# V2_lite.net
KiCad netlist of a schematic drawn in EAGLE
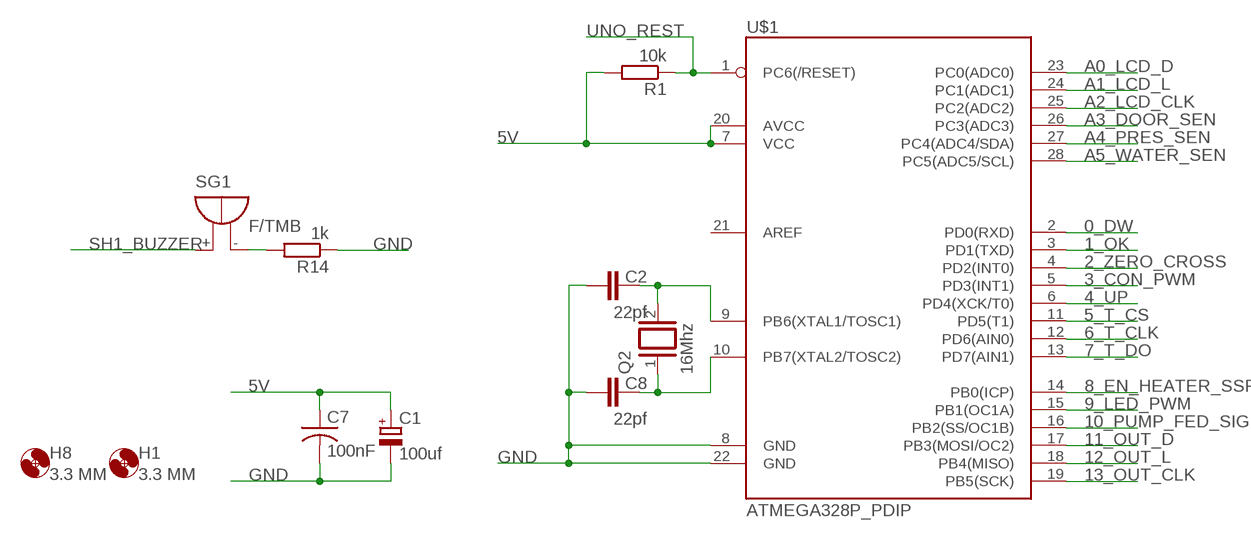
[diagram p0: schematic, sheet 1]
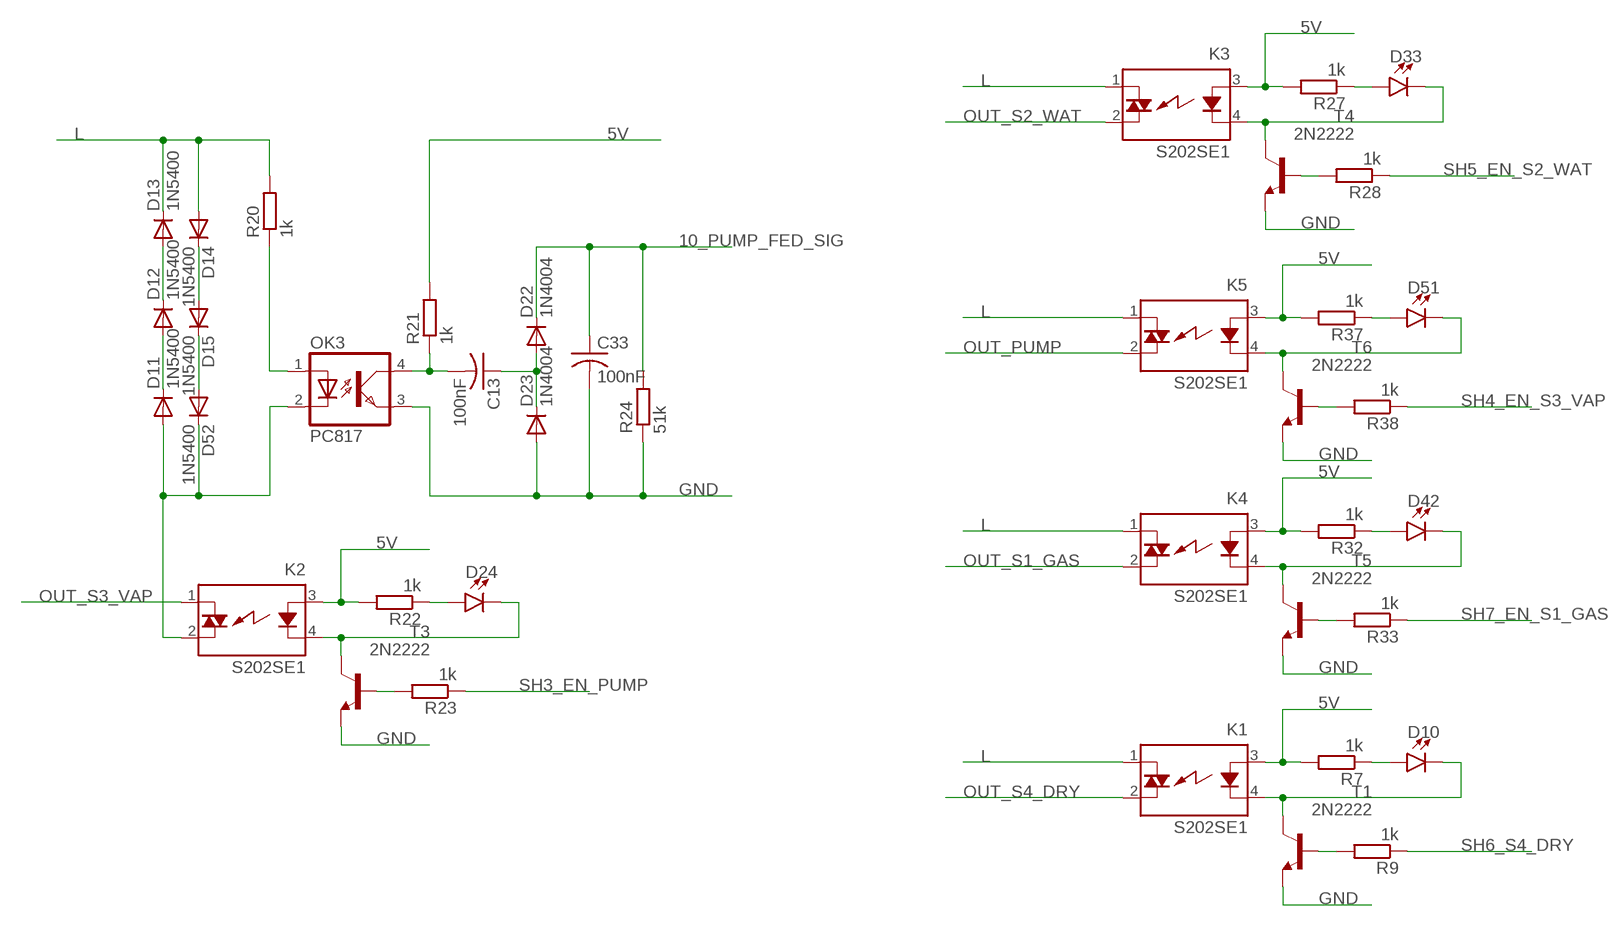
[diagram p1: schematic, sheet 2]
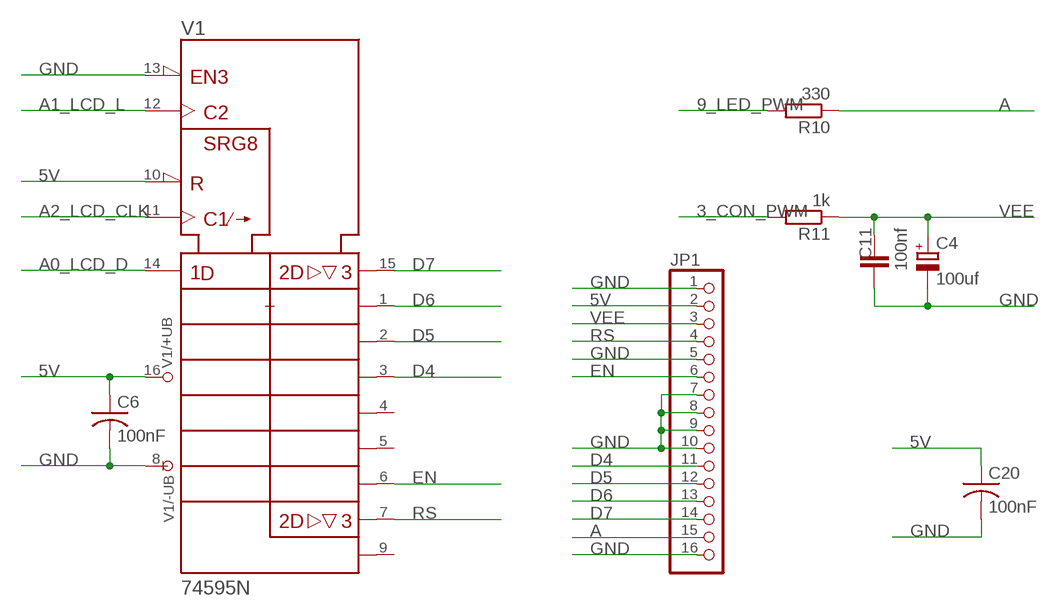
[diagram p2: schematic, sheet 3]
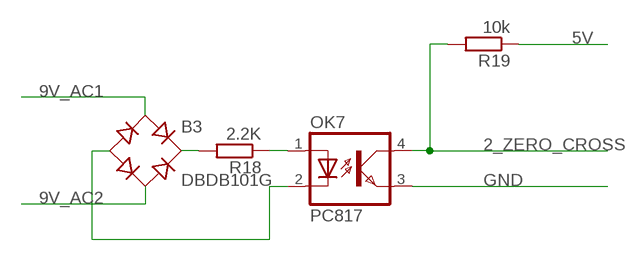
[diagram p3: schematic, sheet 4]
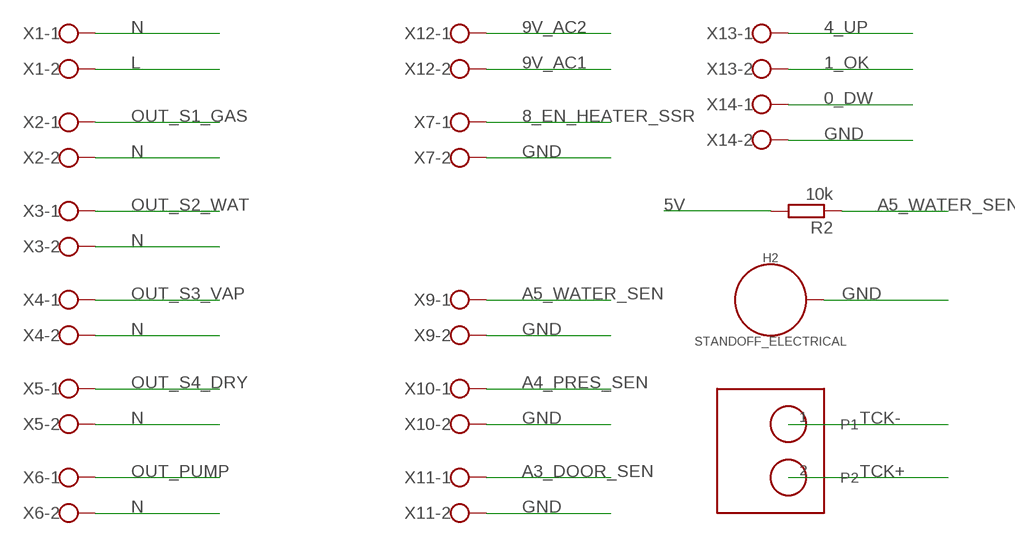
[diagram p4: schematic, sheet 5]
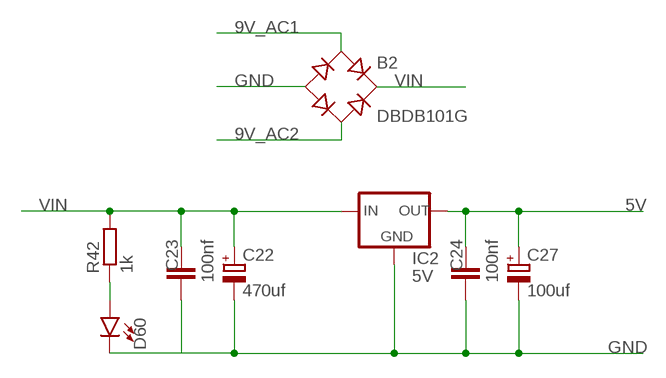
[diagram p5: schematic, sheet 6]
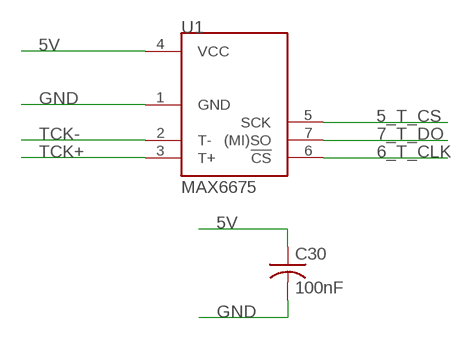
[diagram p6: schematic, sheet 7]
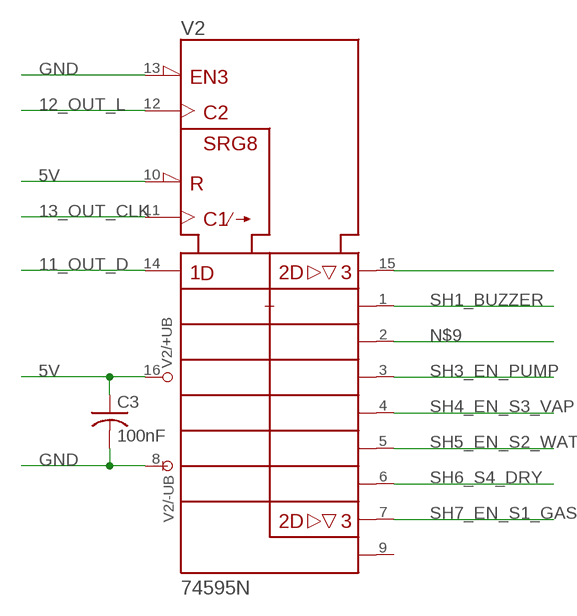
[diagram p7: schematic, sheet 8]

(export (version "E")
  (design (tool "Eeschema 10.0.6"))
  (components
    (comp (ref "C13")
      (value "100nF")
      (footprint "eagle-import:C050-035X075")
      (libsource (lib "eagle-import") (part "C-US050-035X075"))
    )
    (comp (ref "C33")
      (value "100nF")
      (footprint "eagle-import:C050-035X075")
      (libsource (lib "eagle-import") (part "C-US050-035X075"))
    )
    (comp (ref "D10")
      (value "LED5MM")
      (footprint "eagle-import:LED_5MM")
      (libsource (lib "eagle-import") (part "LED5MM"))
    )
    (comp (ref "D11")
      (value "1N5400")
      (footprint "eagle-import:DO201-15")
      (libsource (lib "eagle-import") (part "1N5400"))
    )
    (comp (ref "D12")
      (value "1N5400")
      (footprint "eagle-import:DO201-15")
      (libsource (lib "eagle-import") (part "1N5400"))
    )
    (comp (ref "D13")
      (value "1N5400")
      (footprint "eagle-import:DO201-15")
      (libsource (lib "eagle-import") (part "1N5400"))
    )
    (comp (ref "D14")
      (value "1N5400")
      (footprint "eagle-import:DO201-15")
      (libsource (lib "eagle-import") (part "1N5400"))
    )
    (comp (ref "D15")
      (value "1N5400")
      (footprint "eagle-import:DO201-15")
      (libsource (lib "eagle-import") (part "1N5400"))
    )
    (comp (ref "D22")
      (value "1N4004")
      (footprint "eagle-import:DO41-10")
      (libsource (lib "eagle-import") (part "1N4004"))
    )
    (comp (ref "D23")
      (value "1N4004")
      (footprint "eagle-import:DO41-10")
      (libsource (lib "eagle-import") (part "1N4004"))
    )
    (comp (ref "D24")
      (value "LED5MM")
      (footprint "eagle-import:LED_5MM")
      (libsource (lib "eagle-import") (part "LED5MM"))
    )
    (comp (ref "D33")
      (value "LED5MM")
      (footprint "eagle-import:LED_5MM")
      (libsource (lib "eagle-import") (part "LED5MM"))
    )
    (comp (ref "D42")
      (value "LED5MM")
      (footprint "eagle-import:LED_5MM")
      (libsource (lib "eagle-import") (part "LED5MM"))
    )
    (comp (ref "D51")
      (value "LED5MM")
      (footprint "eagle-import:LED_5MM")
      (libsource (lib "eagle-import") (part "LED5MM"))
    )
    (comp (ref "D52")
      (value "1N5400")
      (footprint "eagle-import:DO201-15")
      (libsource (lib "eagle-import") (part "1N5400"))
    )
    (comp (ref "K1")
      (value "S202SE1")
      (footprint "eagle-import:S2XXEX")
      (libsource (lib "eagle-import") (part "S202SE1"))
    )
    (comp (ref "K2")
      (value "S202SE1")
      (footprint "eagle-import:S2XXEX")
      (libsource (lib "eagle-import") (part "S202SE1"))
    )
    (comp (ref "K3")
      (value "S202SE1")
      (footprint "eagle-import:S2XXEX")
      (libsource (lib "eagle-import") (part "S202SE1"))
    )
    (comp (ref "K4")
      (value "S202SE1")
      (footprint "eagle-import:S2XXEX")
      (libsource (lib "eagle-import") (part "S202SE1"))
    )
    (comp (ref "K5")
      (value "S202SE1")
      (footprint "eagle-import:S2XXEX")
      (libsource (lib "eagle-import") (part "S202SE1"))
    )
    (comp (ref "OK3")
      (value "PC817")
      (footprint "eagle-import:DIL04")
      (libsource (lib "eagle-import") (part "PC817"))
    )
    (comp (ref "R7")
      (value "1k")
      (footprint "eagle-import:0207_10")
      (libsource (lib "eagle-import") (part "R-EU_0207/10"))
    )
    (comp (ref "R9")
      (value "1k")
      (footprint "eagle-import:0207_10")
      (libsource (lib "eagle-import") (part "R-EU_0207/10"))
    )
    (comp (ref "R20")
      (value "1k")
      (footprint "eagle-import:0207_10")
      (libsource (lib "eagle-import") (part "R-EU_0207/10"))
    )
    (comp (ref "R21")
      (value "1k")
      (footprint "eagle-import:0207_10")
      (libsource (lib "eagle-import") (part "R-EU_0207/10"))
    )
    (comp (ref "R22")
      (value "1k")
      (footprint "eagle-import:0207_10")
      (libsource (lib "eagle-import") (part "R-EU_0207/10"))
    )
    (comp (ref "R23")
      (value "1k")
      (footprint "eagle-import:0207_10")
      (libsource (lib "eagle-import") (part "R-EU_0207/10"))
    )
    (comp (ref "R24")
      (value "51k")
      (footprint "eagle-import:0207_10")
      (libsource (lib "eagle-import") (part "R-EU_0207/10"))
    )
    (comp (ref "R27")
      (value "1k")
      (footprint "eagle-import:0207_10")
      (libsource (lib "eagle-import") (part "R-EU_0207/10"))
    )
    (comp (ref "R28")
      (value "1k")
      (footprint "eagle-import:0207_10")
      (libsource (lib "eagle-import") (part "R-EU_0207/10"))
    )
    (comp (ref "R32")
      (value "1k")
      (footprint "eagle-import:0207_10")
      (libsource (lib "eagle-import") (part "R-EU_0207/10"))
    )
    (comp (ref "R33")
      (value "1k")
      (footprint "eagle-import:0207_10")
      (libsource (lib "eagle-import") (part "R-EU_0207/10"))
    )
    (comp (ref "R37")
      (value "1k")
      (footprint "eagle-import:0207_10")
      (libsource (lib "eagle-import") (part "R-EU_0207/10"))
    )
    (comp (ref "R38")
      (value "1k")
      (footprint "eagle-import:0207_10")
      (libsource (lib "eagle-import") (part "R-EU_0207/10"))
    )
    (comp (ref "T1")
      (value "2N2222")
      (footprint "eagle-import:TO92-EBC-OVAL")
      (libsource (lib "eagle-import") (part "2N2222"))
    )
    (comp (ref "T3")
      (value "2N2222")
      (footprint "eagle-import:TO92-EBC-OVAL")
      (libsource (lib "eagle-import") (part "2N2222"))
    )
    (comp (ref "T4")
      (value "2N2222")
      (footprint "eagle-import:TO92-EBC-OVAL")
      (libsource (lib "eagle-import") (part "2N2222"))
    )
    (comp (ref "T5")
      (value "2N2222")
      (footprint "eagle-import:TO92-EBC-OVAL")
      (libsource (lib "eagle-import") (part "2N2222"))
    )
    (comp (ref "T6")
      (value "2N2222")
      (footprint "eagle-import:TO92-EBC-OVAL")
      (libsource (lib "eagle-import") (part "2N2222"))
    )
    (comp (ref "C30")
      (value "100nF")
      (footprint "eagle-import:C050-035X075")
      (libsource (lib "eagle-import") (part "C-US050-035X075"))
    )
    (comp (ref "U1")
      (value "MAX6675")
      (footprint "eagle-import:SOIC8")
      (libsource (lib "eagle-import") (part "MAX6675"))
    )
    (comp (ref "H2")
      (value "STANDOFF_ELECTRICAL")
      (footprint "eagle-import:STANDOFF-ELECTRICAL")
      (libsource (lib "eagle-import") (part "STANDOFF_ELECTRICAL"))
    )
    (comp (ref "R2")
      (value "10k")
      (footprint "eagle-import:0207_10")
      (libsource (lib "eagle-import") (part "R-EU_0207/10"))
    )
    (comp (ref "U$2")
      (value "THERMO_CONNECT")
      (footprint "eagle-import:HW-550")
      (libsource (lib "eagle-import") (part "THERMO_CONNECT"))
    )
    (comp (ref "X1")
      (value "W237-102")
      (footprint "eagle-import:W237-102")
      (fields (field (name "MPN") "237-102"))
      (libsource (lib "eagle-import") (part "W237-102"))
    )
    (comp (ref "X2")
      (value "W237-102")
      (footprint "eagle-import:W237-102")
      (fields (field (name "MPN") "237-102"))
      (libsource (lib "eagle-import") (part "W237-102"))
    )
    (comp (ref "X3")
      (value "W237-102")
      (footprint "eagle-import:W237-102")
      (fields (field (name "MPN") "237-102"))
      (libsource (lib "eagle-import") (part "W237-102"))
    )
    (comp (ref "X4")
      (value "W237-102")
      (footprint "eagle-import:W237-102")
      (fields (field (name "MPN") "237-102"))
      (libsource (lib "eagle-import") (part "W237-102"))
    )
    (comp (ref "X5")
      (value "W237-102")
      (footprint "eagle-import:W237-102")
      (fields (field (name "MPN") "237-102"))
      (libsource (lib "eagle-import") (part "W237-102"))
    )
    (comp (ref "X6")
      (value "W237-102")
      (footprint "eagle-import:W237-102")
      (fields (field (name "MPN") "237-102"))
      (libsource (lib "eagle-import") (part "W237-102"))
    )
    (comp (ref "X7")
      (value "W237-102")
      (footprint "eagle-import:W237-102")
      (fields (field (name "MPN") "237-102"))
      (libsource (lib "eagle-import") (part "W237-102"))
    )
    (comp (ref "X9")
      (value "W237-102")
      (footprint "eagle-import:W237-102")
      (fields (field (name "MPN") "237-102"))
      (libsource (lib "eagle-import") (part "W237-102"))
    )
    (comp (ref "X10")
      (value "W237-102")
      (footprint "eagle-import:W237-102")
      (fields (field (name "MPN") "237-102"))
      (libsource (lib "eagle-import") (part "W237-102"))
    )
    (comp (ref "X11")
      (value "W237-102")
      (footprint "eagle-import:W237-102")
      (fields (field (name "MPN") "237-102"))
      (libsource (lib "eagle-import") (part "W237-102"))
    )
    (comp (ref "X12")
      (value "W237-102")
      (footprint "eagle-import:W237-102")
      (fields (field (name "MPN") "237-102"))
      (libsource (lib "eagle-import") (part "W237-102"))
    )
    (comp (ref "X13")
      (value "W237-102")
      (footprint "eagle-import:W237-102")
      (fields (field (name "MPN") "237-102"))
      (libsource (lib "eagle-import") (part "W237-102"))
    )
    (comp (ref "X14")
      (value "W237-102")
      (footprint "eagle-import:W237-102")
      (fields (field (name "MPN") "237-102"))
      (libsource (lib "eagle-import") (part "W237-102"))
    )
    (comp (ref "B2")
      (value "DBDB101G")
      (footprint "eagle-import:DB")
      (libsource (lib "eagle-import") (part "DB?GDB101"))
    )
    (comp (ref "C22")
      (value "470uf")
      (footprint "eagle-import:E3,5-8")
      (libsource (lib "eagle-import") (part "CPOL-EUE3.5-8"))
    )
    (comp (ref "C23")
      (value "100nf")
      (footprint "eagle-import:C050-030X075")
      (libsource (lib "eagle-import") (part "C-EU050-030X075"))
    )
    (comp (ref "C24")
      (value "100nf")
      (footprint "eagle-import:C050-030X075")
      (libsource (lib "eagle-import") (part "C-EU050-030X075"))
    )
    (comp (ref "C27")
      (value "100uf")
      (footprint "eagle-import:E3,5-8")
      (libsource (lib "eagle-import") (part "CPOL-EUE3.5-8"))
    )
    (comp (ref "D60")
      (value "LED5MM")
      (footprint "eagle-import:LED_5MM")
      (libsource (lib "eagle-import") (part "LED5MM"))
    )
    (comp (ref "IC2")
      (value "5V")
      (footprint "eagle-import:78XXL")
      (libsource (lib "eagle-import") (part "V_REG_78XXSIDE"))
    )
    (comp (ref "R42")
      (value "1k")
      (footprint "eagle-import:0207_10")
      (libsource (lib "eagle-import") (part "R-EU_0207/10"))
    )
    (comp (ref "C1")
      (value "100uf")
      (footprint "eagle-import:E3,5-8")
      (libsource (lib "eagle-import") (part "CPOL-EUE3.5-8"))
    )
    (comp (ref "C2")
      (value "22pf")
      (footprint "eagle-import:C050-030X075")
      (libsource (lib "eagle-import") (part "C-EU050-030X075"))
    )
    (comp (ref "C7")
      (value "100nF")
      (footprint "eagle-import:C050-035X075")
      (libsource (lib "eagle-import") (part "C-US050-035X075"))
    )
    (comp (ref "C8")
      (value "22pf")
      (footprint "eagle-import:C050-030X075")
      (libsource (lib "eagle-import") (part "C-EU050-030X075"))
    )
    (comp (ref "H1")
      (value "3.3 MM")
      (footprint "eagle-import:3,3")
      (libsource (lib "eagle-import") (part "MOUNT-HOLE3.3"))
    )
    (comp (ref "H8")
      (value "3.3 MM")
      (footprint "eagle-import:3,3")
      (libsource (lib "eagle-import") (part "MOUNT-HOLE3.3"))
    )
    (comp (ref "Q2")
      (value "16Mhz")
      (footprint "eagle-import:QS")
      (libsource (lib "eagle-import") (part "XTAL/S"))
    )
    (comp (ref "R1")
      (value "10k")
      (footprint "eagle-import:0207_10")
      (libsource (lib "eagle-import") (part "R-EU_0207/10"))
    )
    (comp (ref "R14")
      (value "1k")
      (footprint "eagle-import:0207_10")
      (libsource (lib "eagle-import") (part "R-EU_0207/10"))
    )
    (comp (ref "SG1")
      (value "F/TMB")
      (footprint "eagle-import:F_TMB")
      (libsource (lib "eagle-import") (part "F/TMB"))
    )
    (comp (ref "U$1")
      (value "ATMEGA328P_PDIP")
      (footprint "eagle-import:DIL-28-3")
      (libsource (lib "eagle-import") (part "ATMEGA328P_PDIP"))
    )
    (comp (ref "B3")
      (value "DBDB101G")
      (footprint "eagle-import:DB")
      (libsource (lib "eagle-import") (part "DB?GDB101"))
    )
    (comp (ref "OK7")
      (value "PC817")
      (footprint "eagle-import:DIL04")
      (libsource (lib "eagle-import") (part "PC817"))
    )
    (comp (ref "R18")
      (value "2.2K")
      (footprint "eagle-import:0207_10")
      (libsource (lib "eagle-import") (part "R-EU_0207/10"))
    )
    (comp (ref "R19")
      (value "10k")
      (footprint "eagle-import:0207_10")
      (libsource (lib "eagle-import") (part "R-EU_0207/10"))
    )
    (comp (ref "C3")
      (value "100nF")
      (footprint "eagle-import:C050-035X075")
      (libsource (lib "eagle-import") (part "C-US050-035X075"))
    )
    (comp (ref "V2")
      (value "74595N")
      (footprint "eagle-import:DIL16")
      (libsource (lib "eagle-import") (part "74595N"))
    )
    (comp (ref "C4")
      (value "100uf")
      (footprint "eagle-import:E3,5-8")
      (libsource (lib "eagle-import") (part "CPOL-EUE3.5-8"))
    )
    (comp (ref "C6")
      (value "100nF")
      (footprint "eagle-import:C050-035X075")
      (libsource (lib "eagle-import") (part "C-US050-035X075"))
    )
    (comp (ref "C11")
      (value "100nf")
      (footprint "eagle-import:C050-030X075")
      (libsource (lib "eagle-import") (part "C-EU050-030X075"))
    )
    (comp (ref "C20")
      (value "100nF")
      (footprint "eagle-import:C050-035X075")
      (libsource (lib "eagle-import") (part "C-US050-035X075"))
    )
    (comp (ref "JP1")
      (value "PINHD-1X16")
      (footprint "eagle-import:1X16")
      (libsource (lib "eagle-import") (part "PINHD-1X16"))
    )
    (comp (ref "R10")
      (value "330")
      (footprint "eagle-import:0207_10")
      (libsource (lib "eagle-import") (part "R-EU_0207/10"))
    )
    (comp (ref "R11")
      (value "1k")
      (footprint "eagle-import:0207_10")
      (libsource (lib "eagle-import") (part "R-EU_0207/10"))
    )
    (comp (ref "V1")
      (value "74595N")
      (footprint "eagle-import:DIL16")
      (libsource (lib "eagle-import") (part "74595N"))
    )
  )
  (nets
    (net (code "1") (name "0_DW") (class "Default")
      (node (ref "U$1") (pin "2") (pinfunction "PD0(RXD)_2") (pintype "bidirectional"))
      (node (ref "X14") (pin "1") (pinfunction "KL_1") (pintype "passive"))
    )
    (net (code "2") (name "1_OK") (class "Default")
      (node (ref "U$1") (pin "3") (pinfunction "PD1(TXD)_3") (pintype "bidirectional"))
      (node (ref "X13") (pin "2") (pinfunction "KL_2") (pintype "passive"))
    )
    (net (code "3") (name "2_ZERO_CROSS") (class "Default")
      (node (ref "OK7") (pin "4") (pinfunction "COL_4") (pintype "passive"))
      (node (ref "R19") (pin "2") (pinfunction "2_2") (pintype "passive"))
      (node (ref "U$1") (pin "4") (pinfunction "PD2(INT0)_4") (pintype "bidirectional"))
    )
    (net (code "4") (name "3_CON_PWM") (class "Default")
      (node (ref "R11") (pin "2") (pinfunction "2_2") (pintype "passive"))
      (node (ref "U$1") (pin "5") (pinfunction "PD3(INT1)_5") (pintype "bidirectional"))
    )
    (net (code "5") (name "4_UP") (class "Default")
      (node (ref "U$1") (pin "6") (pinfunction "PD4(XCK/T0)_6") (pintype "bidirectional"))
      (node (ref "X13") (pin "1") (pinfunction "KL_1") (pintype "passive"))
    )
    (net (code "6") (name "5V") (class "Default")
      (node (ref "C1") (pin "+") (pinfunction "+_+") (pintype "passive"))
      (node (ref "C20") (pin "1") (pinfunction "1_1") (pintype "passive"))
      (node (ref "C24") (pin "2") (pinfunction "2_2") (pintype "passive"))
      (node (ref "C27") (pin "+") (pinfunction "+_+") (pintype "passive"))
      (node (ref "C3") (pin "1") (pinfunction "1_1") (pintype "passive"))
      (node (ref "C30") (pin "1") (pinfunction "1_1") (pintype "passive"))
      (node (ref "C6") (pin "1") (pinfunction "1_1") (pintype "passive"))
      (node (ref "C7") (pin "1") (pinfunction "1_1") (pintype "passive"))
      (node (ref "IC2") (pin "OUT") (pinfunction "OUT_OUT") (pintype "output"))
      (node (ref "JP1") (pin "2") (pinfunction "2_2") (pintype "passive"))
      (node (ref "K1") (pin "3") (pinfunction "A_3") (pintype "passive"))
      (node (ref "K2") (pin "3") (pinfunction "A_3") (pintype "passive"))
      (node (ref "K3") (pin "3") (pinfunction "A_3") (pintype "passive"))
      (node (ref "K4") (pin "3") (pinfunction "A_3") (pintype "passive"))
      (node (ref "K5") (pin "3") (pinfunction "A_3") (pintype "passive"))
      (node (ref "R1") (pin "2") (pinfunction "2_2") (pintype "passive"))
      (node (ref "R19") (pin "1") (pinfunction "1_1") (pintype "passive"))
      (node (ref "R2") (pin "2") (pinfunction "2_2") (pintype "passive"))
      (node (ref "R21") (pin "2") (pinfunction "2_2") (pintype "passive"))
      (node (ref "R22") (pin "2") (pinfunction "2_2") (pintype "passive"))
      (node (ref "R27") (pin "2") (pinfunction "2_2") (pintype "passive"))
      (node (ref "R32") (pin "2") (pinfunction "2_2") (pintype "passive"))
      (node (ref "R37") (pin "2") (pinfunction "2_2") (pintype "passive"))
      (node (ref "R7") (pin "2") (pinfunction "2_2") (pintype "passive"))
      (node (ref "U$1") (pin "20") (pinfunction "AVCC_20") (pintype "bidirectional"))
      (node (ref "U$1") (pin "7") (pinfunction "VCC_7") (pintype "bidirectional"))
      (node (ref "U1") (pin "4") (pinfunction "VCC_4") (pintype "bidirectional"))
      (node (ref "V1") (pin "10") (pinfunction "~{SRCLR}_10") (pintype "input"))
      (node (ref "V1") (pin "16") (pinfunction "+UB_16") (pintype "power_in"))
      (node (ref "V2") (pin "10") (pinfunction "~{SRCLR}_10") (pintype "input"))
      (node (ref "V2") (pin "16") (pinfunction "+UB_16") (pintype "power_in"))
    )
    (net (code "7") (name "5_T_CS") (class "Default")
      (node (ref "U$1") (pin "11") (pinfunction "PD5(T1)_11") (pintype "bidirectional"))
      (node (ref "U1") (pin "5") (pinfunction "SCK_5") (pintype "bidirectional"))
    )
    (net (code "8") (name "6_T_CLK") (class "Default")
      (node (ref "U$1") (pin "12") (pinfunction "PD6(AIN0)_12") (pintype "bidirectional"))
      (node (ref "U1") (pin "6") (pinfunction "~{CS}_6") (pintype "bidirectional"))
    )
    (net (code "9") (name "7_T_DO") (class "Default")
      (node (ref "U$1") (pin "13") (pinfunction "PD7(AIN1)_13") (pintype "bidirectional"))
      (node (ref "U1") (pin "7") (pinfunction "(MI)SO_7") (pintype "bidirectional"))
    )
    (net (code "10") (name "8_EN_HEATER_SSR") (class "Default")
      (node (ref "U$1") (pin "14") (pinfunction "PB0(ICP)_14") (pintype "bidirectional"))
      (node (ref "X7") (pin "1") (pinfunction "KL_1") (pintype "passive"))
    )
    (net (code "11") (name "9V_AC1") (class "Default")
      (node (ref "B2") (pin "AC1") (pinfunction "AC1_AC1") (pintype "passive"))
      (node (ref "B3") (pin "AC1") (pinfunction "AC1_AC1") (pintype "passive"))
      (node (ref "X12") (pin "2") (pinfunction "KL_2") (pintype "passive"))
    )
    (net (code "12") (name "9V_AC2") (class "Default")
      (node (ref "B2") (pin "AC2") (pinfunction "AC2_AC2") (pintype "passive"))
      (node (ref "B3") (pin "AC2") (pinfunction "AC2_AC2") (pintype "passive"))
      (node (ref "X12") (pin "1") (pinfunction "KL_1") (pintype "passive"))
    )
    (net (code "13") (name "9_LED_PWM") (class "Default")
      (node (ref "R10") (pin "2") (pinfunction "2_2") (pintype "passive"))
      (node (ref "U$1") (pin "15") (pinfunction "PB1(OC1A)_15") (pintype "bidirectional"))
    )
    (net (code "14") (name "10_PUMP_FED_SIG") (class "Default")
      (node (ref "C33") (pin "1") (pinfunction "1_1") (pintype "passive"))
      (node (ref "D22") (pin "C") (pinfunction "C_C") (pintype "passive"))
      (node (ref "R24") (pin "2") (pinfunction "2_2") (pintype "passive"))
      (node (ref "U$1") (pin "16") (pinfunction "PB2(SS/OC1B)_16") (pintype "bidirectional"))
    )
    (net (code "15") (name "11_OUT_D") (class "Default")
      (node (ref "U$1") (pin "17") (pinfunction "PB3(MOSI/OC2)_17") (pintype "bidirectional"))
      (node (ref "V2") (pin "14") (pinfunction "SER_14") (pintype "input"))
    )
    (net (code "16") (name "12_OUT_L") (class "Default")
      (node (ref "U$1") (pin "18") (pinfunction "PB4(MISO)_18") (pintype "bidirectional"))
      (node (ref "V2") (pin "12") (pinfunction "RCK_12") (pintype "input"))
    )
    (net (code "17") (name "13_OUT_CLK") (class "Default")
      (node (ref "U$1") (pin "19") (pinfunction "PB5(SCK)_19") (pintype "bidirectional"))
      (node (ref "V2") (pin "11") (pinfunction "SRCK_11") (pintype "input"))
    )
    (net (code "18") (name "A") (class "Default")
      (node (ref "JP1") (pin "15") (pinfunction "15_15") (pintype "passive"))
      (node (ref "R10") (pin "1") (pinfunction "1_1") (pintype "passive"))
    )
    (net (code "19") (name "A0_LCD_D") (class "Default")
      (node (ref "U$1") (pin "23") (pinfunction "PC0(ADC0)_23") (pintype "bidirectional"))
      (node (ref "V1") (pin "14") (pinfunction "SER_14") (pintype "input"))
    )
    (net (code "20") (name "A1_LCD_L") (class "Default")
      (node (ref "U$1") (pin "24") (pinfunction "PC1(ADC1)_24") (pintype "bidirectional"))
      (node (ref "V1") (pin "12") (pinfunction "RCK_12") (pintype "input"))
    )
    (net (code "21") (name "A2_LCD_CLK") (class "Default")
      (node (ref "U$1") (pin "25") (pinfunction "PC2(ADC2)_25") (pintype "bidirectional"))
      (node (ref "V1") (pin "11") (pinfunction "SRCK_11") (pintype "input"))
    )
    (net (code "22") (name "A3_DOOR_SEN") (class "Default")
      (node (ref "U$1") (pin "26") (pinfunction "PC3(ADC3)_26") (pintype "bidirectional"))
      (node (ref "X11") (pin "1") (pinfunction "KL_1") (pintype "passive"))
    )
    (net (code "23") (name "A4_PRES_SEN") (class "Default")
      (node (ref "U$1") (pin "27") (pinfunction "PC4(ADC4/SDA)_27") (pintype "bidirectional"))
      (node (ref "X10") (pin "1") (pinfunction "KL_1") (pintype "passive"))
    )
    (net (code "24") (name "A5_WATER_SEN") (class "Default")
      (node (ref "R2") (pin "1") (pinfunction "1_1") (pintype "passive"))
      (node (ref "U$1") (pin "28") (pinfunction "PC5(ADC5/SCL)_28") (pintype "bidirectional"))
      (node (ref "X9") (pin "1") (pinfunction "KL_1") (pintype "passive"))
    )
    (net (code "25") (name "D4") (class "Default")
      (node (ref "JP1") (pin "11") (pinfunction "11_11") (pintype "passive"))
      (node (ref "V1") (pin "3") (pinfunction "QD_3") (pintype "tri_state"))
    )
    (net (code "26") (name "D5") (class "Default")
      (node (ref "JP1") (pin "12") (pinfunction "12_12") (pintype "passive"))
      (node (ref "V1") (pin "2") (pinfunction "QC_2") (pintype "tri_state"))
    )
    (net (code "27") (name "D6") (class "Default")
      (node (ref "JP1") (pin "13") (pinfunction "13_13") (pintype "passive"))
      (node (ref "V1") (pin "1") (pinfunction "QB_1") (pintype "tri_state"))
    )
    (net (code "28") (name "D7") (class "Default")
      (node (ref "JP1") (pin "14") (pinfunction "14_14") (pintype "passive"))
      (node (ref "V1") (pin "15") (pinfunction "QA_15") (pintype "tri_state"))
    )
    (net (code "29") (name "EN") (class "Default")
      (node (ref "JP1") (pin "6") (pinfunction "6_6") (pintype "passive"))
      (node (ref "V1") (pin "6") (pinfunction "QG_6") (pintype "tri_state"))
    )
    (net (code "30") (name "GND") (class "Default")
      (node (ref "B2") (pin "-") (pinfunction "-_-") (pintype "passive"))
      (node (ref "C1") (pin "-") (pinfunction "-_-") (pintype "passive"))
      (node (ref "C11") (pin "1") (pinfunction "1_1") (pintype "passive"))
      (node (ref "C2") (pin "1") (pinfunction "1_1") (pintype "passive"))
      (node (ref "C20") (pin "2") (pinfunction "2_2") (pintype "passive"))
      (node (ref "C22") (pin "-") (pinfunction "-_-") (pintype "passive"))
      (node (ref "C23") (pin "1") (pinfunction "1_1") (pintype "passive"))
      (node (ref "C24") (pin "1") (pinfunction "1_1") (pintype "passive"))
      (node (ref "C27") (pin "-") (pinfunction "-_-") (pintype "passive"))
      (node (ref "C3") (pin "2") (pinfunction "2_2") (pintype "passive"))
      (node (ref "C30") (pin "2") (pinfunction "2_2") (pintype "passive"))
      (node (ref "C33") (pin "2") (pinfunction "2_2") (pintype "passive"))
      (node (ref "C4") (pin "-") (pinfunction "-_-") (pintype "passive"))
      (node (ref "C6") (pin "2") (pinfunction "2_2") (pintype "passive"))
      (node (ref "C7") (pin "2") (pinfunction "2_2") (pintype "passive"))
      (node (ref "C8") (pin "1") (pinfunction "1_1") (pintype "passive"))
      (node (ref "D23") (pin "A") (pinfunction "A_A") (pintype "passive"))
      (node (ref "D60") (pin "K") (pinfunction "C_K") (pintype "passive"))
      (node (ref "H2") (pin "P1") (pinfunction "P$1_P1") (pintype "bidirectional"))
      (node (ref "IC2") (pin "GND") (pinfunction "GND_GND") (pintype "input"))
      (node (ref "JP1") (pin "1") (pinfunction "1_1") (pintype "passive"))
      (node (ref "JP1") (pin "10") (pinfunction "10_10") (pintype "passive"))
      (node (ref "JP1") (pin "16") (pinfunction "16_16") (pintype "passive"))
      (node (ref "JP1") (pin "5") (pinfunction "5_5") (pintype "passive"))
      (node (ref "JP1") (pin "7") (pinfunction "7_7") (pintype "passive"))
      (node (ref "JP1") (pin "8") (pinfunction "8_8") (pintype "passive"))
      (node (ref "JP1") (pin "9") (pinfunction "9_9") (pintype "passive"))
      (node (ref "OK3") (pin "3") (pinfunction "EMIT_3") (pintype "passive"))
      (node (ref "OK7") (pin "3") (pinfunction "EMIT_3") (pintype "passive"))
      (node (ref "R14") (pin "1") (pinfunction "1_1") (pintype "passive"))
      (node (ref "R24") (pin "1") (pinfunction "1_1") (pintype "passive"))
      (node (ref "T1") (pin "E") (pinfunction "E_E") (pintype "passive"))
      (node (ref "T3") (pin "E") (pinfunction "E_E") (pintype "passive"))
      (node (ref "T4") (pin "E") (pinfunction "E_E") (pintype "passive"))
      (node (ref "T5") (pin "E") (pinfunction "E_E") (pintype "passive"))
      (node (ref "T6") (pin "E") (pinfunction "E_E") (pintype "passive"))
      (node (ref "U$1") (pin "22") (pinfunction "GND_22") (pintype "bidirectional"))
      (node (ref "U$1") (pin "8") (pinfunction "GND_8") (pintype "bidirectional"))
      (node (ref "U1") (pin "1") (pinfunction "GND_1") (pintype "bidirectional"))
      (node (ref "V1") (pin "13") (pinfunction "~{G}_13") (pintype "input"))
      (node (ref "V1") (pin "8") (pinfunction "-UB_8") (pintype "power_in"))
      (node (ref "V2") (pin "13") (pinfunction "~{G}_13") (pintype "input"))
      (node (ref "V2") (pin "8") (pinfunction "-UB_8") (pintype "power_in"))
      (node (ref "X10") (pin "2") (pinfunction "KL_2") (pintype "passive"))
      (node (ref "X11") (pin "2") (pinfunction "KL_2") (pintype "passive"))
      (node (ref "X14") (pin "2") (pinfunction "KL_2") (pintype "passive"))
      (node (ref "X7") (pin "2") (pinfunction "KL_2") (pintype "passive"))
      (node (ref "X9") (pin "2") (pinfunction "KL_2") (pintype "passive"))
    )
    (net (code "31") (name "L") (class "Default")
      (node (ref "D13") (pin "C") (pinfunction "C_C") (pintype "passive"))
      (node (ref "D14") (pin "A") (pinfunction "A_A") (pintype "passive"))
      (node (ref "K1") (pin "1") (pinfunction "DS1_1") (pintype "passive"))
      (node (ref "K3") (pin "1") (pinfunction "DS1_1") (pintype "passive"))
      (node (ref "K4") (pin "1") (pinfunction "DS1_1") (pintype "passive"))
      (node (ref "K5") (pin "1") (pinfunction "DS1_1") (pintype "passive"))
      (node (ref "R20") (pin "2") (pinfunction "2_2") (pintype "passive"))
      (node (ref "X1") (pin "2") (pinfunction "KL_2") (pintype "passive"))
    )
    (net (code "32") (name "N") (class "Default")
      (node (ref "X1") (pin "1") (pinfunction "KL_1") (pintype "passive"))
      (node (ref "X2") (pin "2") (pinfunction "KL_2") (pintype "passive"))
      (node (ref "X3") (pin "2") (pinfunction "KL_2") (pintype "passive"))
      (node (ref "X4") (pin "2") (pinfunction "KL_2") (pintype "passive"))
      (node (ref "X5") (pin "2") (pinfunction "KL_2") (pintype "passive"))
      (node (ref "X6") (pin "2") (pinfunction "KL_2") (pintype "passive"))
    )
    (net (code "33") (name "N$9") (class "Default")
      (node (ref "V2") (pin "2") (pinfunction "QC_2") (pintype "tri_state"))
    )
    (net (code "34") (name "Net-(B3-Pad+)") (class "Default")
      (node (ref "B3") (pin "+") (pinfunction "+_+") (pintype "passive"))
      (node (ref "R18") (pin "2") (pinfunction "2_2") (pintype "passive"))
    )
    (net (code "35") (name "Net-(C13-Pad1)") (class "Default")
      (node (ref "C13") (pin "1") (pinfunction "1_1") (pintype "passive"))
      (node (ref "D22") (pin "A") (pinfunction "A_A") (pintype "passive"))
      (node (ref "D23") (pin "C") (pinfunction "C_C") (pintype "passive"))
    )
    (net (code "36") (name "Net-(D10-C)") (class "Default")
      (node (ref "D10") (pin "K") (pinfunction "C_K") (pintype "passive"))
      (node (ref "K1") (pin "4") (pinfunction "K_4") (pintype "passive"))
      (node (ref "T1") (pin "C") (pinfunction "C_C") (pintype "passive"))
    )
    (net (code "37") (name "Net-(D10-PadA)") (class "Default")
      (node (ref "D10") (pin "A") (pinfunction "A_A") (pintype "passive"))
      (node (ref "R7") (pin "1") (pinfunction "1_1") (pintype "passive"))
    )
    (net (code "38") (name "Net-(D11-PadC)") (class "Default")
      (node (ref "D11") (pin "C") (pinfunction "C_C") (pintype "passive"))
      (node (ref "D12") (pin "A") (pinfunction "A_A") (pintype "passive"))
    )
    (net (code "39") (name "Net-(D12-PadC)") (class "Default")
      (node (ref "D12") (pin "C") (pinfunction "C_C") (pintype "passive"))
      (node (ref "D13") (pin "A") (pinfunction "A_A") (pintype "passive"))
    )
    (net (code "40") (name "Net-(D14-PadC)") (class "Default")
      (node (ref "D14") (pin "C") (pinfunction "C_C") (pintype "passive"))
      (node (ref "D15") (pin "A") (pinfunction "A_A") (pintype "passive"))
    )
    (net (code "41") (name "Net-(D15-PadC)") (class "Default")
      (node (ref "D15") (pin "C") (pinfunction "C_C") (pintype "passive"))
      (node (ref "D52") (pin "A") (pinfunction "A_A") (pintype "passive"))
    )
    (net (code "42") (name "Net-(D24-C)") (class "Default")
      (node (ref "D24") (pin "K") (pinfunction "C_K") (pintype "passive"))
      (node (ref "K2") (pin "4") (pinfunction "K_4") (pintype "passive"))
      (node (ref "T3") (pin "C") (pinfunction "C_C") (pintype "passive"))
    )
    (net (code "43") (name "Net-(D24-PadA)") (class "Default")
      (node (ref "D24") (pin "A") (pinfunction "A_A") (pintype "passive"))
      (node (ref "R22") (pin "1") (pinfunction "1_1") (pintype "passive"))
    )
    (net (code "44") (name "Net-(D33-C)") (class "Default")
      (node (ref "D33") (pin "K") (pinfunction "C_K") (pintype "passive"))
      (node (ref "K3") (pin "4") (pinfunction "K_4") (pintype "passive"))
      (node (ref "T4") (pin "C") (pinfunction "C_C") (pintype "passive"))
    )
    (net (code "45") (name "Net-(D33-PadA)") (class "Default")
      (node (ref "D33") (pin "A") (pinfunction "A_A") (pintype "passive"))
      (node (ref "R27") (pin "1") (pinfunction "1_1") (pintype "passive"))
    )
    (net (code "46") (name "Net-(D42-C)") (class "Default")
      (node (ref "D42") (pin "K") (pinfunction "C_K") (pintype "passive"))
      (node (ref "K4") (pin "4") (pinfunction "K_4") (pintype "passive"))
      (node (ref "T5") (pin "C") (pinfunction "C_C") (pintype "passive"))
    )
    (net (code "47") (name "Net-(D42-PadA)") (class "Default")
      (node (ref "D42") (pin "A") (pinfunction "A_A") (pintype "passive"))
      (node (ref "R32") (pin "1") (pinfunction "1_1") (pintype "passive"))
    )
    (net (code "48") (name "Net-(D51-C)") (class "Default")
      (node (ref "D51") (pin "K") (pinfunction "C_K") (pintype "passive"))
      (node (ref "K5") (pin "4") (pinfunction "K_4") (pintype "passive"))
      (node (ref "T6") (pin "C") (pinfunction "C_C") (pintype "passive"))
    )
    (net (code "49") (name "Net-(D51-PadA)") (class "Default")
      (node (ref "D51") (pin "A") (pinfunction "A_A") (pintype "passive"))
      (node (ref "R37") (pin "1") (pinfunction "1_1") (pintype "passive"))
    )
    (net (code "50") (name "Net-(D60-PadA)") (class "Default")
      (node (ref "D60") (pin "A") (pinfunction "A_A") (pintype "passive"))
      (node (ref "R42") (pin "1") (pinfunction "1_1") (pintype "passive"))
    )
    (net (code "51") (name "Net-(K2-DS2)") (class "Default")
      (node (ref "D11") (pin "A") (pinfunction "A_A") (pintype "passive"))
      (node (ref "D52") (pin "C") (pinfunction "C_C") (pintype "passive"))
      (node (ref "K2") (pin "2") (pinfunction "DS2_2") (pintype "passive"))
      (node (ref "OK3") (pin "2") (pinfunction "C_2") (pintype "passive"))
    )
    (net (code "52") (name "Net-(OK3-A)") (class "Default")
      (node (ref "OK3") (pin "1") (pinfunction "A_1") (pintype "passive"))
      (node (ref "R20") (pin "1") (pinfunction "1_1") (pintype "passive"))
    )
    (net (code "53") (name "Net-(OK3-COL)") (class "Default")
      (node (ref "C13") (pin "2") (pinfunction "2_2") (pintype "passive"))
      (node (ref "OK3") (pin "4") (pinfunction "COL_4") (pintype "passive"))
      (node (ref "R21") (pin "1") (pinfunction "1_1") (pintype "passive"))
    )
    (net (code "54") (name "Net-(OK7-A)") (class "Default")
      (node (ref "OK7") (pin "1") (pinfunction "A_1") (pintype "passive"))
      (node (ref "R18") (pin "1") (pinfunction "1_1") (pintype "passive"))
    )
    (net (code "55") (name "Net-(OK7-C)") (class "Default")
      (node (ref "B3") (pin "-") (pinfunction "-_-") (pintype "passive"))
      (node (ref "OK7") (pin "2") (pinfunction "C_2") (pintype "passive"))
    )
    (net (code "56") (name "Net-(R9-Pad2)") (class "Default")
      (node (ref "R9") (pin "2") (pinfunction "2_2") (pintype "passive"))
      (node (ref "T1") (pin "B") (pinfunction "B_B") (pintype "passive"))
    )
    (net (code "57") (name "Net-(R14-Pad2)") (class "Default")
      (node (ref "R14") (pin "2") (pinfunction "2_2") (pintype "passive"))
      (node (ref "SG1") (pin "-") (pinfunction "-_-") (pintype "passive"))
    )
    (net (code "58") (name "Net-(R23-Pad2)") (class "Default")
      (node (ref "R23") (pin "2") (pinfunction "2_2") (pintype "passive"))
      (node (ref "T3") (pin "B") (pinfunction "B_B") (pintype "passive"))
    )
    (net (code "59") (name "Net-(R28-Pad2)") (class "Default")
      (node (ref "R28") (pin "2") (pinfunction "2_2") (pintype "passive"))
      (node (ref "T4") (pin "B") (pinfunction "B_B") (pintype "passive"))
    )
    (net (code "60") (name "Net-(R33-Pad2)") (class "Default")
      (node (ref "R33") (pin "2") (pinfunction "2_2") (pintype "passive"))
      (node (ref "T5") (pin "B") (pinfunction "B_B") (pintype "passive"))
    )
    (net (code "61") (name "Net-(R38-Pad2)") (class "Default")
      (node (ref "R38") (pin "2") (pinfunction "2_2") (pintype "passive"))
      (node (ref "T6") (pin "B") (pinfunction "B_B") (pintype "passive"))
    )
    (net (code "62") (name "Net-(U$1-PB6(XTAL1{slash}TOSC1))") (class "Default")
      (node (ref "C2") (pin "2") (pinfunction "2_2") (pintype "passive"))
      (node (ref "Q2") (pin "2") (pinfunction "2_2") (pintype "passive"))
      (node (ref "U$1") (pin "9") (pinfunction "PB6(XTAL1/TOSC1)_9") (pintype "bidirectional"))
    )
    (net (code "63") (name "Net-(U$1-PB7(XTAL2{slash}TOSC2))") (class "Default")
      (node (ref "C8") (pin "2") (pinfunction "2_2") (pintype "passive"))
      (node (ref "Q2") (pin "1") (pinfunction "1_1") (pintype "passive"))
      (node (ref "U$1") (pin "10") (pinfunction "PB7(XTAL2/TOSC2)_10") (pintype "bidirectional"))
    )
    (net (code "64") (name "OUT_PUMP") (class "Default")
      (node (ref "K5") (pin "2") (pinfunction "DS2_2") (pintype "passive"))
      (node (ref "X6") (pin "1") (pinfunction "KL_1") (pintype "passive"))
    )
    (net (code "65") (name "OUT_S1_GAS") (class "Default")
      (node (ref "K4") (pin "2") (pinfunction "DS2_2") (pintype "passive"))
      (node (ref "X2") (pin "1") (pinfunction "KL_1") (pintype "passive"))
    )
    (net (code "66") (name "OUT_S2_WAT") (class "Default")
      (node (ref "K3") (pin "2") (pinfunction "DS2_2") (pintype "passive"))
      (node (ref "X3") (pin "1") (pinfunction "KL_1") (pintype "passive"))
    )
    (net (code "67") (name "OUT_S3_VAP") (class "Default")
      (node (ref "K2") (pin "1") (pinfunction "DS1_1") (pintype "passive"))
      (node (ref "X4") (pin "1") (pinfunction "KL_1") (pintype "passive"))
    )
    (net (code "68") (name "OUT_S4_DRY") (class "Default")
      (node (ref "K1") (pin "2") (pinfunction "DS2_2") (pintype "passive"))
      (node (ref "X5") (pin "1") (pinfunction "KL_1") (pintype "passive"))
    )
    (net (code "69") (name "RS") (class "Default")
      (node (ref "JP1") (pin "4") (pinfunction "4_4") (pintype "passive"))
      (node (ref "V1") (pin "7") (pinfunction "QH_7") (pintype "tri_state"))
    )
    (net (code "70") (name "SH1_BUZZER") (class "Default")
      (node (ref "SG1") (pin "+") (pinfunction "+_+") (pintype "passive"))
      (node (ref "V2") (pin "1") (pinfunction "QB_1") (pintype "tri_state"))
    )
    (net (code "71") (name "SH3_EN_PUMP") (class "Default")
      (node (ref "R23") (pin "1") (pinfunction "1_1") (pintype "passive"))
      (node (ref "V2") (pin "3") (pinfunction "QD_3") (pintype "tri_state"))
    )
    (net (code "72") (name "SH4_EN_S3_VAP") (class "Default")
      (node (ref "R38") (pin "1") (pinfunction "1_1") (pintype "passive"))
      (node (ref "V2") (pin "4") (pinfunction "QE_4") (pintype "tri_state"))
    )
    (net (code "73") (name "SH5_EN_S2_WAT") (class "Default")
      (node (ref "R28") (pin "1") (pinfunction "1_1") (pintype "passive"))
      (node (ref "V2") (pin "5") (pinfunction "QF_5") (pintype "tri_state"))
    )
    (net (code "74") (name "SH6_S4_DRY") (class "Default")
      (node (ref "R9") (pin "1") (pinfunction "1_1") (pintype "passive"))
      (node (ref "V2") (pin "6") (pinfunction "QG_6") (pintype "tri_state"))
    )
    (net (code "75") (name "SH7_EN_S1_GAS") (class "Default")
      (node (ref "R33") (pin "1") (pinfunction "1_1") (pintype "passive"))
      (node (ref "V2") (pin "7") (pinfunction "QH_7") (pintype "tri_state"))
    )
    (net (code "76") (name "TCK+") (class "Default")
      (node (ref "U$2") (pin "2") (pinfunction "P2_2") (pintype "bidirectional"))
      (node (ref "U1") (pin "3") (pinfunction "T+_3") (pintype "bidirectional"))
    )
    (net (code "77") (name "TCK-") (class "Default")
      (node (ref "U$2") (pin "1") (pinfunction "P1_1") (pintype "bidirectional"))
      (node (ref "U1") (pin "2") (pinfunction "T-_2") (pintype "bidirectional"))
    )
    (net (code "78") (name "UNO_REST") (class "Default")
      (node (ref "R1") (pin "1") (pinfunction "1_1") (pintype "passive"))
      (node (ref "U$1") (pin "1") (pinfunction "PC6(/RESET)_1") (pintype "bidirectional"))
    )
    (net (code "79") (name "VEE") (class "Default")
      (node (ref "C11") (pin "2") (pinfunction "2_2") (pintype "passive"))
      (node (ref "C4") (pin "+") (pinfunction "+_+") (pintype "passive"))
      (node (ref "JP1") (pin "3") (pinfunction "3_3") (pintype "passive"))
      (node (ref "R11") (pin "1") (pinfunction "1_1") (pintype "passive"))
    )
    (net (code "80") (name "VIN") (class "Default")
      (node (ref "B2") (pin "+") (pinfunction "+_+") (pintype "passive"))
      (node (ref "C22") (pin "+") (pinfunction "+_+") (pintype "passive"))
      (node (ref "C23") (pin "2") (pinfunction "2_2") (pintype "passive"))
      (node (ref "IC2") (pin "IN") (pinfunction "IN_IN") (pintype "input"))
      (node (ref "R42") (pin "2") (pinfunction "2_2") (pintype "passive"))
    )
    (net (code "81") (name "unconnected-(U$1-AREF-Pad21)") (class "Default")
      (node (ref "U$1") (pin "21") (pinfunction "AREF_21") (pintype "bidirectional"))
    )
    (net (code "82") (name "unconnected-(V1C-QE-Pad4)") (class "Default")
      (node (ref "V1") (pin "4") (pinfunction "QE_4") (pintype "tri_state"))
    )
    (net (code "83") (name "unconnected-(V1C-QF-Pad5)") (class "Default")
      (node (ref "V1") (pin "5") (pinfunction "QF_5") (pintype "tri_state"))
    )
    (net (code "84") (name "unconnected-(V1C-QH*-Pad9)") (class "Default")
      (node (ref "V1") (pin "9") (pinfunction "QH*_9") (pintype "output"))
    )
    (net (code "85") (name "unconnected-(V2C-QA-Pad15)") (class "Default")
      (node (ref "V2") (pin "15") (pinfunction "QA_15") (pintype "tri_state"))
    )
    (net (code "86") (name "unconnected-(V2C-QH*-Pad9)") (class "Default")
      (node (ref "V2") (pin "9") (pinfunction "QH*_9") (pintype "output"))
    )
  )
)
